# 3DAM_V2.net
KiCad netlist of a schematic drawn in EAGLE
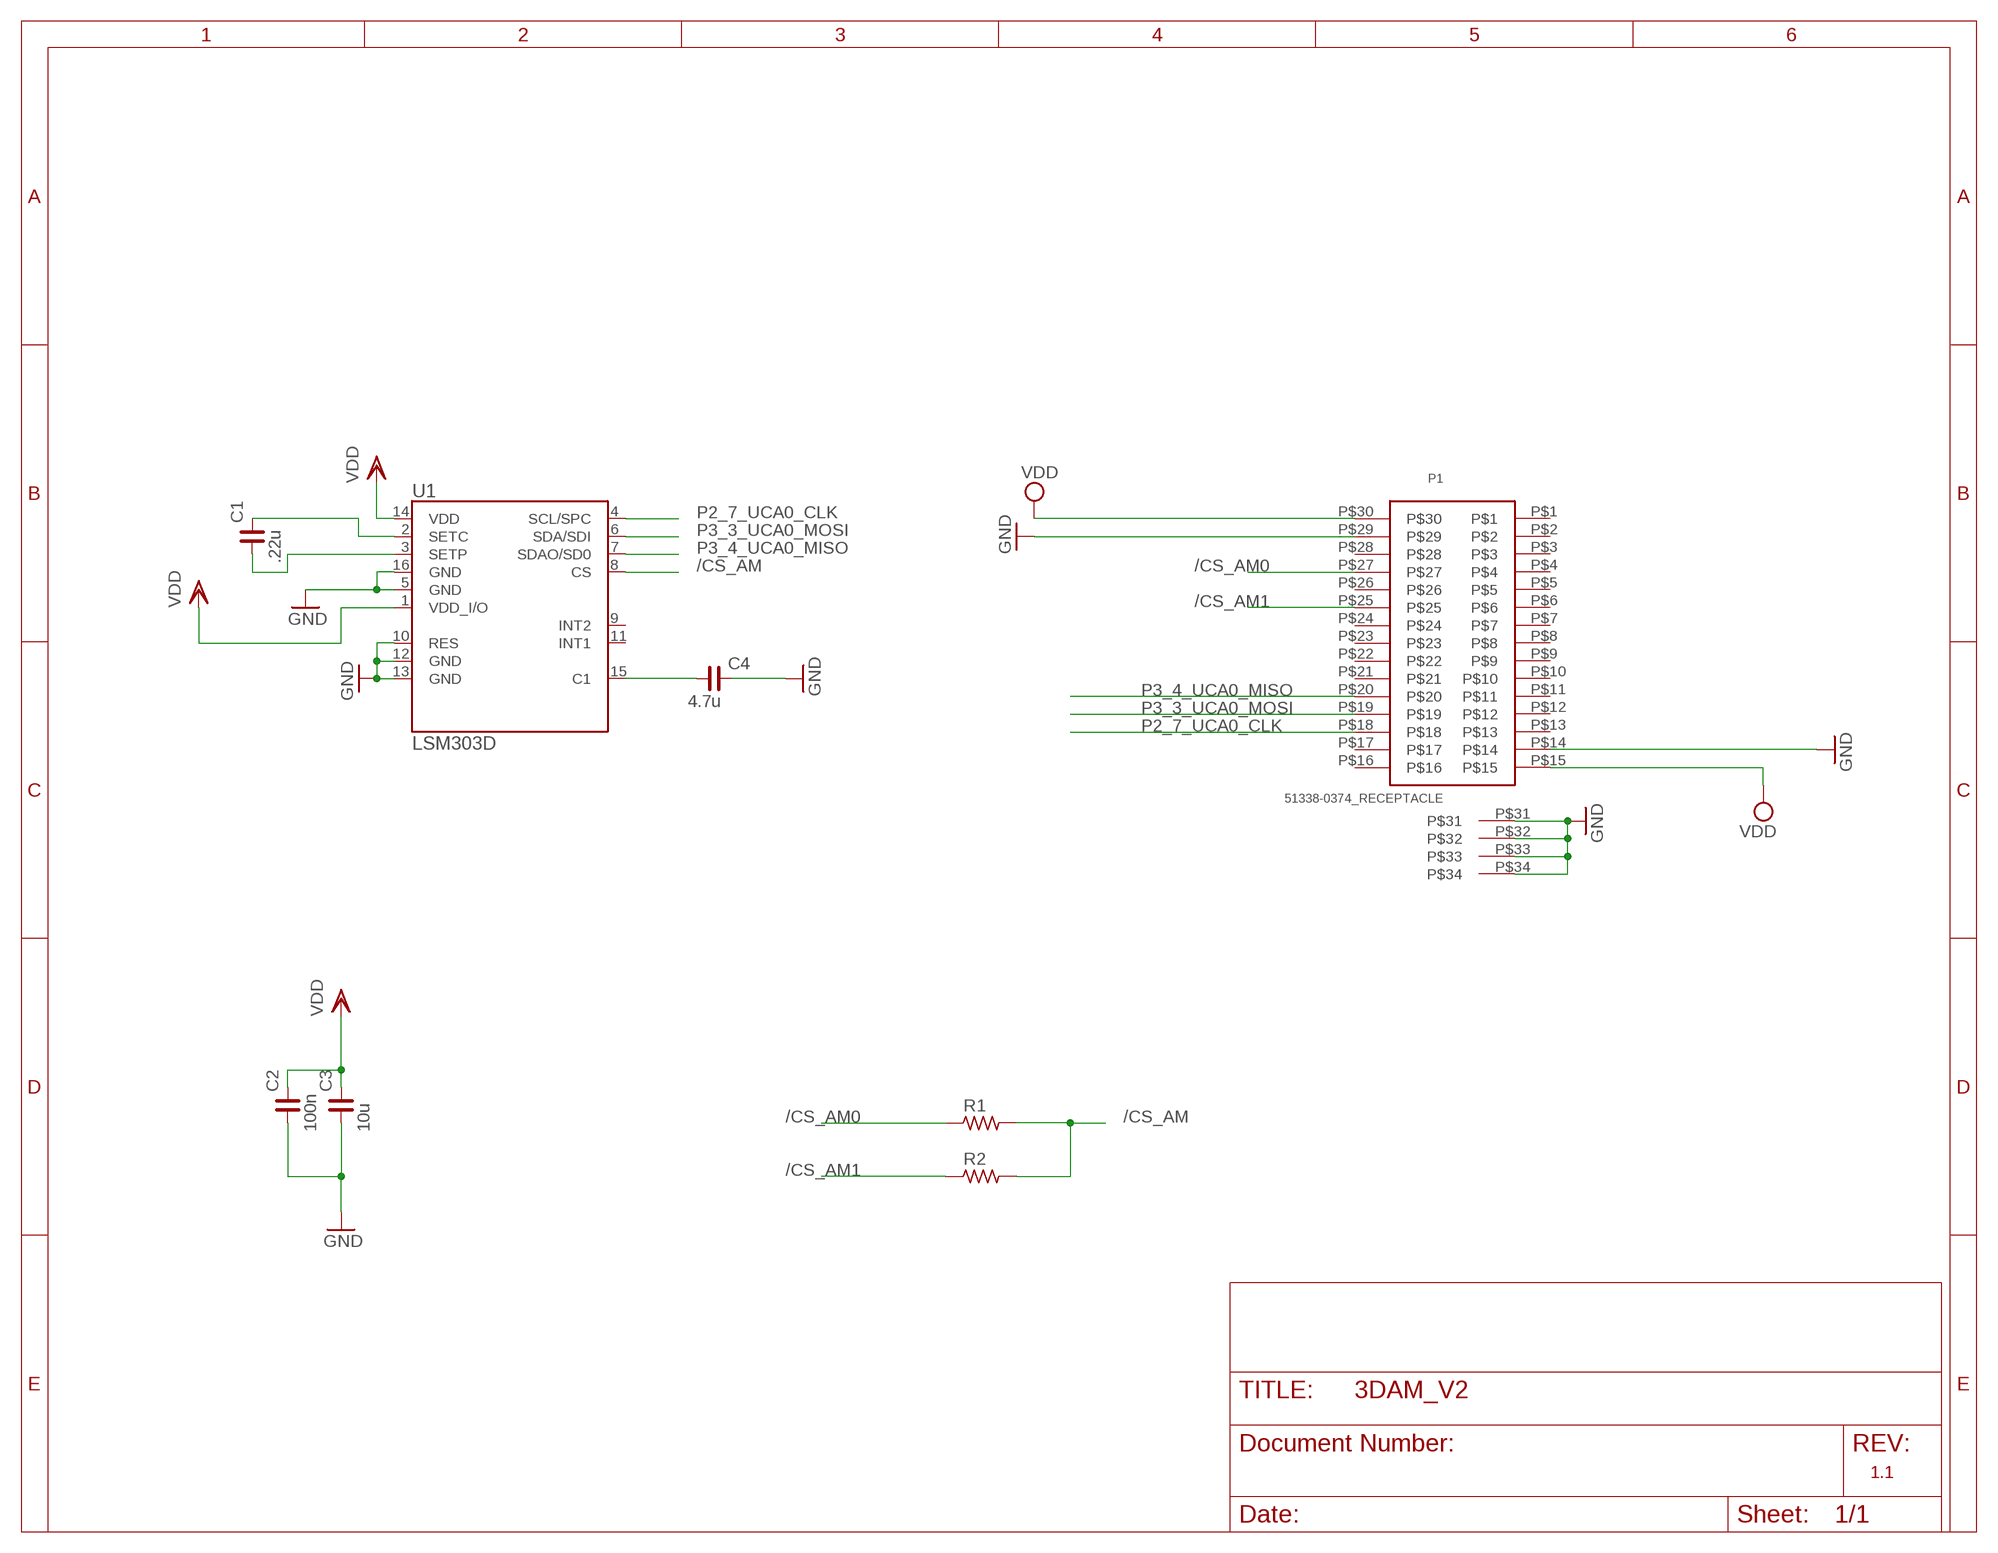
[diagram p0: schematic, sheet 1]

(export (version "E")
  (design (tool "Eeschema 10.0.6"))
  (components
    (comp (ref "C1")
      (value ".22u")
      (footprint "eagle-import:C0402")
      (libsource (lib "eagle-import") (part "C_0402"))
    )
    (comp (ref "C2")
      (value "100n")
      (footprint "eagle-import:C0402")
      (libsource (lib "eagle-import") (part "C_0402"))
    )
    (comp (ref "C3")
      (value "10u")
      (footprint "eagle-import:C0402")
      (libsource (lib "eagle-import") (part "C_0402"))
    )
    (comp (ref "C4")
      (value "4.7u")
      (footprint "eagle-import:C0402")
      (libsource (lib "eagle-import") (part "C_0402"))
    )
    (comp (ref "P1")
      (value "51338-0374_RECEPTACLE")
      (footprint "eagle-import:51338-0374_RECEPTACLE")
      (libsource (lib "eagle-import") (part "51338-0374_RECEPTACLE"))
    )
    (comp (ref "R1")
      (value "R_0402")
      (footprint "eagle-import:R0402")
      (libsource (lib "eagle-import") (part "R_0402"))
    )
    (comp (ref "R2")
      (value "R_0402")
      (footprint "eagle-import:R0402")
      (libsource (lib "eagle-import") (part "R_0402"))
    )
    (comp (ref "U1")
      (value "LSM303D")
      (footprint "eagle-import:LGA16-3MM")
      (libsource (lib "eagle-import") (part "LSM303D"))
    )
  )
  (nets
    (net (code "1") (name "/P2_7_UCA0_CLK") (class "Default")
      (node (ref "P1") (pin "P$18") (pinfunction "P$18_P$18") (pintype "bidirectional"))
      (node (ref "U1") (pin "4") (pinfunction "SCL/SPC_4") (pintype "bidirectional"))
    )
    (net (code "2") (name "/P3_3_UCA0_MOSI") (class "Default")
      (node (ref "P1") (pin "P$19") (pinfunction "P$19_P$19") (pintype "bidirectional"))
      (node (ref "U1") (pin "6") (pinfunction "SDA/SDI_6") (pintype "bidirectional"))
    )
    (net (code "3") (name "/P3_4_UCA0_MISO") (class "Default")
      (node (ref "P1") (pin "P$20") (pinfunction "P$20_P$20") (pintype "bidirectional"))
      (node (ref "U1") (pin "7") (pinfunction "SDAO/SD0_7") (pintype "bidirectional"))
    )
    (net (code "4") (name "/{slash}CS_AM") (class "Default")
      (node (ref "R1") (pin "2") (pinfunction "2_2") (pintype "passive"))
      (node (ref "R2") (pin "2") (pinfunction "2_2") (pintype "passive"))
      (node (ref "U1") (pin "8") (pinfunction "CS_8") (pintype "bidirectional"))
    )
    (net (code "5") (name "/{slash}CS_AM0") (class "Default")
      (node (ref "P1") (pin "P$27") (pinfunction "P$27_P$27") (pintype "bidirectional"))
      (node (ref "R1") (pin "1") (pinfunction "1_1") (pintype "passive"))
    )
    (net (code "6") (name "/{slash}CS_AM1") (class "Default")
      (node (ref "P1") (pin "P$25") (pinfunction "P$25_P$25") (pintype "bidirectional"))
      (node (ref "R2") (pin "1") (pinfunction "1_1") (pintype "passive"))
    )
    (net (code "7") (name "GND") (class "Default")
      (node (ref "C2") (pin "1") (pinfunction "1_1") (pintype "passive"))
      (node (ref "C3") (pin "1") (pinfunction "1_1") (pintype "passive"))
      (node (ref "C4") (pin "2") (pinfunction "2_2") (pintype "passive"))
      (node (ref "P1") (pin "P$14") (pinfunction "P$14_P$14") (pintype "bidirectional"))
      (node (ref "P1") (pin "P$29") (pinfunction "P$29_P$29") (pintype "bidirectional"))
      (node (ref "P1") (pin "P$31") (pinfunction "P$31_P$31") (pintype "bidirectional"))
      (node (ref "P1") (pin "P$32") (pinfunction "P$32_P$32") (pintype "bidirectional"))
      (node (ref "P1") (pin "P$33") (pinfunction "P$33_P$33") (pintype "bidirectional"))
      (node (ref "P1") (pin "P$34") (pinfunction "P$34_P$34") (pintype "bidirectional"))
      (node (ref "U1") (pin "10") (pinfunction "RES_10") (pintype "bidirectional"))
      (node (ref "U1") (pin "12") (pinfunction "GND_12") (pintype "bidirectional"))
      (node (ref "U1") (pin "13") (pinfunction "GND_13") (pintype "bidirectional"))
      (node (ref "U1") (pin "16") (pinfunction "GND_16") (pintype "bidirectional"))
      (node (ref "U1") (pin "5") (pinfunction "GND_5") (pintype "bidirectional"))
    )
    (net (code "8") (name "Net-(U1-C1)") (class "Default")
      (node (ref "C4") (pin "1") (pinfunction "1_1") (pintype "passive"))
      (node (ref "U1") (pin "15") (pinfunction "C1_15") (pintype "bidirectional"))
    )
    (net (code "9") (name "Net-(U1-SETC)") (class "Default")
      (node (ref "C1") (pin "2") (pinfunction "2_2") (pintype "passive"))
      (node (ref "U1") (pin "2") (pinfunction "SETC_2") (pintype "bidirectional"))
    )
    (net (code "10") (name "Net-(U1-SETP)") (class "Default")
      (node (ref "C1") (pin "1") (pinfunction "1_1") (pintype "passive"))
      (node (ref "U1") (pin "3") (pinfunction "SETP_3") (pintype "bidirectional"))
    )
    (net (code "11") (name "VDD") (class "Default")
      (node (ref "C2") (pin "2") (pinfunction "2_2") (pintype "passive"))
      (node (ref "C3") (pin "2") (pinfunction "2_2") (pintype "passive"))
      (node (ref "P1") (pin "P$15") (pinfunction "P$15_P$15") (pintype "bidirectional"))
      (node (ref "P1") (pin "P$30") (pinfunction "P$30_P$30") (pintype "bidirectional"))
      (node (ref "U1") (pin "1") (pinfunction "VDD_I/O_1") (pintype "bidirectional"))
      (node (ref "U1") (pin "14") (pinfunction "VDD_14") (pintype "bidirectional"))
    )
    (net (code "12") (name "unconnected-(P1-PadP$1)") (class "Default")
      (node (ref "P1") (pin "P$1") (pinfunction "P$1_P$1") (pintype "bidirectional"))
    )
    (net (code "13") (name "unconnected-(P1-PadP$2)") (class "Default")
      (node (ref "P1") (pin "P$2") (pinfunction "P$2_P$2") (pintype "bidirectional"))
    )
    (net (code "14") (name "unconnected-(P1-PadP$3)") (class "Default")
      (node (ref "P1") (pin "P$3") (pinfunction "P$3_P$3") (pintype "bidirectional"))
    )
    (net (code "15") (name "unconnected-(P1-PadP$4)") (class "Default")
      (node (ref "P1") (pin "P$4") (pinfunction "P$4_P$4") (pintype "bidirectional"))
    )
    (net (code "16") (name "unconnected-(P1-PadP$5)") (class "Default")
      (node (ref "P1") (pin "P$5") (pinfunction "P$5_P$5") (pintype "bidirectional"))
    )
    (net (code "17") (name "unconnected-(P1-PadP$6)") (class "Default")
      (node (ref "P1") (pin "P$6") (pinfunction "P$6_P$6") (pintype "bidirectional"))
    )
    (net (code "18") (name "unconnected-(P1-PadP$7)") (class "Default")
      (node (ref "P1") (pin "P$7") (pinfunction "P$7_P$7") (pintype "bidirectional"))
    )
    (net (code "19") (name "unconnected-(P1-PadP$8)") (class "Default")
      (node (ref "P1") (pin "P$8") (pinfunction "P$8_P$8") (pintype "bidirectional"))
    )
    (net (code "20") (name "unconnected-(P1-PadP$9)") (class "Default")
      (node (ref "P1") (pin "P$9") (pinfunction "P$9_P$9") (pintype "bidirectional"))
    )
    (net (code "21") (name "unconnected-(P1-PadP$10)") (class "Default")
      (node (ref "P1") (pin "P$10") (pinfunction "P$10_P$10") (pintype "bidirectional"))
    )
    (net (code "22") (name "unconnected-(P1-PadP$11)") (class "Default")
      (node (ref "P1") (pin "P$11") (pinfunction "P$11_P$11") (pintype "bidirectional"))
    )
    (net (code "23") (name "unconnected-(P1-PadP$12)") (class "Default")
      (node (ref "P1") (pin "P$12") (pinfunction "P$12_P$12") (pintype "bidirectional"))
    )
    (net (code "24") (name "unconnected-(P1-PadP$13)") (class "Default")
      (node (ref "P1") (pin "P$13") (pinfunction "P$13_P$13") (pintype "bidirectional"))
    )
    (net (code "25") (name "unconnected-(P1-PadP$16)") (class "Default")
      (node (ref "P1") (pin "P$16") (pinfunction "P$16_P$16") (pintype "bidirectional"))
    )
    (net (code "26") (name "unconnected-(P1-PadP$17)") (class "Default")
      (node (ref "P1") (pin "P$17") (pinfunction "P$17_P$17") (pintype "bidirectional"))
    )
    (net (code "27") (name "unconnected-(P1-PadP$21)") (class "Default")
      (node (ref "P1") (pin "P$21") (pinfunction "P$21_P$21") (pintype "bidirectional"))
    )
    (net (code "28") (name "unconnected-(P1-PadP$22)") (class "Default")
      (node (ref "P1") (pin "P$22") (pinfunction "P$22_P$22") (pintype "bidirectional"))
    )
    (net (code "29") (name "unconnected-(P1-PadP$23)") (class "Default")
      (node (ref "P1") (pin "P$23") (pinfunction "P$23_P$23") (pintype "bidirectional"))
    )
    (net (code "30") (name "unconnected-(P1-PadP$24)") (class "Default")
      (node (ref "P1") (pin "P$24") (pinfunction "P$24_P$24") (pintype "bidirectional"))
    )
    (net (code "31") (name "unconnected-(P1-PadP$26)") (class "Default")
      (node (ref "P1") (pin "P$26") (pinfunction "P$26_P$26") (pintype "bidirectional"))
    )
    (net (code "32") (name "unconnected-(P1-PadP$28)") (class "Default")
      (node (ref "P1") (pin "P$28") (pinfunction "P$28_P$28") (pintype "bidirectional"))
    )
    (net (code "33") (name "unconnected-(U1-INT1-Pad11)") (class "Default")
      (node (ref "U1") (pin "11") (pinfunction "INT1_11") (pintype "bidirectional"))
    )
    (net (code "34") (name "unconnected-(U1-INT2-Pad9)") (class "Default")
      (node (ref "U1") (pin "9") (pinfunction "INT2_9") (pintype "bidirectional"))
    )
  )
)
